# TDAR_VER_88.net
KiCad netlist of a schematic drawn in EAGLE
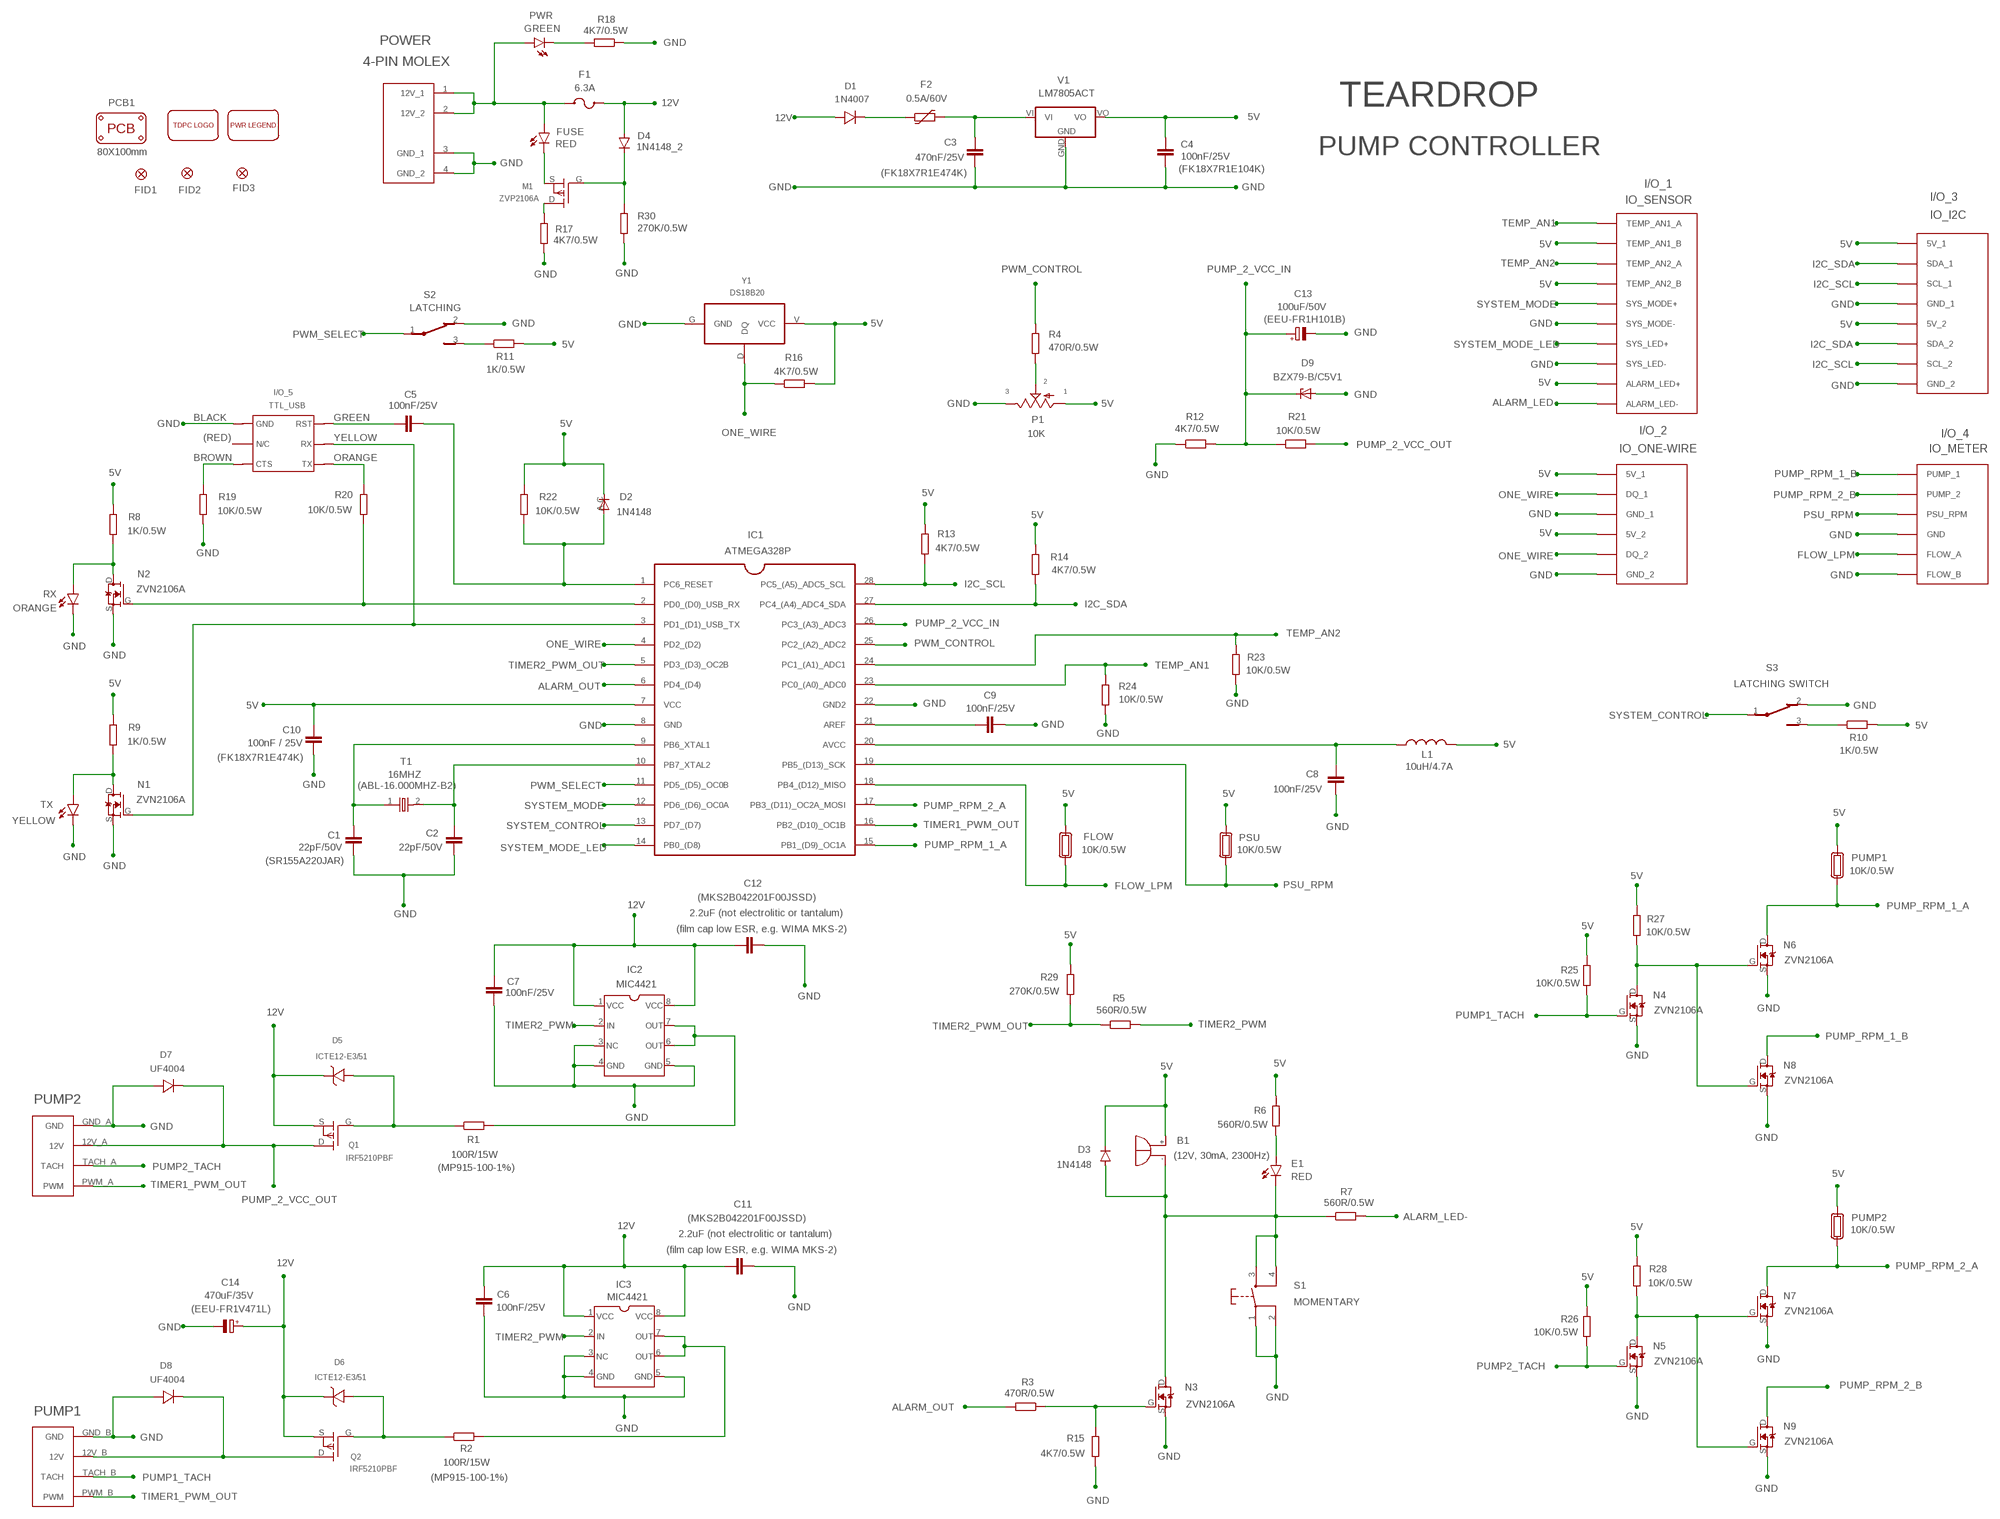
[diagram p0: schematic, sheet 1]

(export (version "E")
  (design (tool "Eeschema 10.0.6"))
  (components
    (comp (ref "B1")
      (value "(12V, 30mA, 2300Hz)")
      (footprint "eagle-import:F_TMB")
      (libsource (lib "eagle-import") (part "F/TMB"))
    )
    (comp (ref "C1")
      (value "22pF/50V")
      (footprint "eagle-import:MLCC_CERAMIC_12")
      (libsource (lib "eagle-import") (part "MLCC_CERAMIC_12"))
    )
    (comp (ref "C2")
      (value "22pF/50V")
      (footprint "eagle-import:MLCC_CERAMIC_11")
      (libsource (lib "eagle-import") (part "MLCC_CERAMIC_11"))
    )
    (comp (ref "C3")
      (value "470nF/25V")
      (footprint "eagle-import:MLCC_CERAMIC_8")
      (libsource (lib "eagle-import") (part "MLCC_CERAMIC_8"))
    )
    (comp (ref "C4")
      (value "100nF/25V")
      (footprint "eagle-import:MLCC_CERAMIC")
      (libsource (lib "eagle-import") (part "MLCC_CERAMIC"))
    )
    (comp (ref "C5")
      (value "100nF/25V")
      (footprint "eagle-import:MLCC_CERAMIC")
      (libsource (lib "eagle-import") (part "MLCC_CERAMIC"))
    )
    (comp (ref "C6")
      (value "100nF/25V")
      (footprint "eagle-import:MLCC_CERAMIC")
      (libsource (lib "eagle-import") (part "MLCC_CERAMIC"))
    )
    (comp (ref "C7")
      (value "100nF/25V")
      (footprint "eagle-import:MLCC_CERAMIC")
      (libsource (lib "eagle-import") (part "MLCC_CERAMIC"))
    )
    (comp (ref "C8")
      (value "100nF/25V")
      (footprint "eagle-import:MLCC_CERAMIC_7")
      (libsource (lib "eagle-import") (part "MLCC_CERAMIC_7"))
    )
    (comp (ref "C9")
      (value "100nF/25V")
      (footprint "eagle-import:MLCC_CERAMIC_7")
      (libsource (lib "eagle-import") (part "MLCC_CERAMIC_7"))
    )
    (comp (ref "C10")
      (value "100nF / 25V")
      (footprint "eagle-import:MLCC_CERAMIC_6")
      (libsource (lib "eagle-import") (part "MLCC_CERAMIC_6"))
    )
    (comp (ref "C11")
      (value "(MKS2B042201F00JSSD)")
      (footprint "eagle-import:WIMA_CAPACITOR")
      (libsource (lib "eagle-import") (part "WIMA_CAPACITOR"))
    )
    (comp (ref "C12")
      (value "(MKS2B042201F00JSSD)")
      (footprint "eagle-import:WIMA_CAPACITOR")
      (libsource (lib "eagle-import") (part "WIMA_CAPACITOR"))
    )
    (comp (ref "C13")
      (value "100uF/50V")
      (footprint "eagle-import:E5-10,5")
      (libsource (lib "eagle-import") (part "CPOL-EUE5-10.5"))
    )
    (comp (ref "C14")
      (value "470uF/35V")
      (footprint "eagle-import:E5-10,5")
      (libsource (lib "eagle-import") (part "CPOL-EUE5-10.5"))
    )
    (comp (ref "D1")
      (value "1N4007")
      (footprint "eagle-import:UF4004")
      (libsource (lib "eagle-import") (part "UF4004"))
    )
    (comp (ref "D2")
      (value "1N4148")
      (footprint "eagle-import:DO35-7")
      (libsource (lib "eagle-import") (part "1N4148DO35-7"))
    )
    (comp (ref "D3")
      (value "1N4148")
      (footprint "eagle-import:1N4148")
      (libsource (lib "eagle-import") (part "1N4148"))
    )
    (comp (ref "D4")
      (value "1N4148_2")
      (footprint "eagle-import:1N4148_2")
      (libsource (lib "eagle-import") (part "1N4148_2"))
    )
    (comp (ref "D5")
      (value "ICTE12-E3/51")
      (footprint "eagle-import:TVS_DIODE")
      (libsource (lib "eagle-import") (part "TVS_DIODE"))
    )
    (comp (ref "D6")
      (value "ICTE12-E3/51")
      (footprint "eagle-import:TVS_DIODE")
      (libsource (lib "eagle-import") (part "TVS_DIODE"))
    )
    (comp (ref "D7")
      (value "UF4004")
      (footprint "eagle-import:UF4004_2")
      (libsource (lib "eagle-import") (part "UF4004_2"))
    )
    (comp (ref "D8")
      (value "UF4004")
      (footprint "eagle-import:UF4004_2")
      (libsource (lib "eagle-import") (part "UF4004_2"))
    )
    (comp (ref "D9")
      (value "BZX79-B/C5V1")
      (footprint "eagle-import:DO34Z7")
      (libsource (lib "eagle-import") (part "BZX90"))
    )
    (comp (ref "E1")
      (value "RED")
      (footprint "eagle-import:LED_5_HORIZONTAL")
      (libsource (lib "eagle-import") (part "LED_5_HORIZONTAL"))
    )
    (comp (ref "F1")
      (value "6.3A")
      (footprint "eagle-import:FUSE_GLASS")
      (libsource (lib "eagle-import") (part "FUSE_GLASS"))
    )
    (comp (ref "F2")
      (value "0.5A/60V")
      (footprint "eagle-import:PTC")
      (libsource (lib "eagle-import") (part "PTC"))
    )
    (comp (ref "FID1")
      (value "FIDUCIAL1X2")
      (footprint "eagle-import:FIDUCIAL-1X2")
      (libsource (lib "eagle-import") (part "FIDUCIAL1X2"))
    )
    (comp (ref "FID2")
      (value "FIDUCIAL1X2")
      (footprint "eagle-import:FIDUCIAL-1X2")
      (libsource (lib "eagle-import") (part "FIDUCIAL1X2"))
    )
    (comp (ref "FID3")
      (value "FIDUCIAL1X2")
      (footprint "eagle-import:FIDUCIAL-1X2")
      (libsource (lib "eagle-import") (part "FIDUCIAL1X2"))
    )
    (comp (ref "FLOW")
      (value "10K/0.5W")
      (footprint "eagle-import:RESISTOR_SOCKET_TOP")
      (libsource (lib "eagle-import") (part "RESISTOR_SOCKET_TOP"))
    )
    (comp (ref "FUSE")
      (value "RED")
      (footprint "eagle-import:LED_1.8_LEFT")
      (libsource (lib "eagle-import") (part "LED_1.8_LEFT"))
    )
    (comp (ref "I/O_1")
      (value "IO_SENSOR")
      (footprint "eagle-import:IO_GENERAL_4")
      (libsource (lib "eagle-import") (part "IO_GENERAL_4"))
    )
    (comp (ref "I/O_2")
      (value "IO_ONE-WIRE")
      (footprint "eagle-import:I0_ONE-WIRE")
      (libsource (lib "eagle-import") (part "IO_ONE-WIRE"))
    )
    (comp (ref "I/O_3")
      (value "IO_I2C")
      (footprint "eagle-import:IO_I2C")
      (libsource (lib "eagle-import") (part "IO_I2C"))
    )
    (comp (ref "I/O_4")
      (value "IO_METER")
      (footprint "eagle-import:IO_SENSOR_4")
      (libsource (lib "eagle-import") (part "IO_SENSOR_4"))
    )
    (comp (ref "I/O_5")
      (value "TTL_USB")
      (footprint "eagle-import:TTL_USB_7")
      (libsource (lib "eagle-import") (part "TTL_USB_7"))
    )
    (comp (ref "IC1")
      (value "ATMEGA328P")
      (footprint "eagle-import:ATMEGA328P")
      (libsource (lib "eagle-import") (part "ATMEGA328P"))
    )
    (comp (ref "IC2")
      (value "MIC4421")
      (footprint "eagle-import:TC4420")
      (libsource (lib "eagle-import") (part "TC4420"))
    )
    (comp (ref "IC3")
      (value "MIC4421")
      (footprint "eagle-import:TC4420")
      (libsource (lib "eagle-import") (part "TC4420"))
    )
    (comp (ref "L1")
      (value "10uH/4.7A")
      (footprint "eagle-import:IRF24")
      (libsource (lib "eagle-import") (part "L-USIRF-24"))
    )
    (comp (ref "M1")
      (value "ZVP2106A")
      (footprint "eagle-import:ZVP2106A")
      (libsource (lib "eagle-import") (part "ZVP2106A"))
    )
    (comp (ref "N1")
      (value "ZVN2106A")
      (footprint "eagle-import:ZVN2106A")
      (libsource (lib "eagle-import") (part "ZVN2106A"))
    )
    (comp (ref "N2")
      (value "ZVN2106A")
      (footprint "eagle-import:ZVN2106A")
      (libsource (lib "eagle-import") (part "ZVN2106A"))
    )
    (comp (ref "N3")
      (value "ZVN2106A")
      (footprint "eagle-import:ZVN2106A")
      (libsource (lib "eagle-import") (part "ZVN2106A"))
    )
    (comp (ref "N4")
      (value "ZVN2106A")
      (footprint "eagle-import:ZVN2106A")
      (libsource (lib "eagle-import") (part "ZVN2106A"))
    )
    (comp (ref "N5")
      (value "ZVN2106A")
      (footprint "eagle-import:ZVN2106A")
      (libsource (lib "eagle-import") (part "ZVN2106A"))
    )
    (comp (ref "N6")
      (value "ZVN2106A")
      (footprint "eagle-import:ZVN2106A")
      (libsource (lib "eagle-import") (part "ZVN2106A"))
    )
    (comp (ref "N7")
      (value "ZVN2106A")
      (footprint "eagle-import:ZVN2106A")
      (libsource (lib "eagle-import") (part "ZVN2106A"))
    )
    (comp (ref "N8")
      (value "ZVN2106A")
      (footprint "eagle-import:ZVN2106A")
      (libsource (lib "eagle-import") (part "ZVN2106A"))
    )
    (comp (ref "N9")
      (value "ZVN2106A")
      (footprint "eagle-import:ZVN2106A")
      (libsource (lib "eagle-import") (part "ZVN2106A"))
    )
    (comp (ref "P1")
      (value "10K")
      (footprint "eagle-import:POTENTIMETER_SQUARE")
      (libsource (lib "eagle-import") (part "POTENTIMETER_SQUARE"))
    )
    (comp (ref "PCB1")
      (value "80X100mm")
      (footprint "eagle-import:DP10080_V1")
      (libsource (lib "eagle-import") (part "PCB_DP_RECTANGLE-80X100"))
    )
    (comp (ref "POWER")
      (value "4-PIN MOLEX")
      (footprint "eagle-import:MOLEX_4PIN_2")
      (libsource (lib "eagle-import") (part "MOLEX_4PIN_2"))
    )
    (comp (ref "PSU")
      (value "10K/0.5W")
      (footprint "eagle-import:RESISTOR_SOCKET_TOP")
      (libsource (lib "eagle-import") (part "RESISTOR_SOCKET_TOP"))
    )
    (comp (ref "PUMP1")
      (value "10K/0.5W")
      (footprint "eagle-import:RESISTOR_SOCKET_TOP")
      (libsource (lib "eagle-import") (part "RESISTOR_SOCKET_TOP"))
    )
    (comp (ref "PUMP2")
      (value "10K/0.5W")
      (footprint "eagle-import:RESISTOR_SOCKET_TOP")
      (libsource (lib "eagle-import") (part "RESISTOR_SOCKET_TOP"))
    )
    (comp (ref "PUMP_2")
      (value "PUMP2")
      (footprint "eagle-import:MOLEX_POWER_8_PIN_HORIZONTAL_2")
      (libsource (lib "eagle-import") (part "MOLEX_POWER_8_PIN_HORIZONTAL_2"))
    )
    (comp (ref "PWR")
      (value "GREEN")
      (footprint "eagle-import:LED_1.8_LEFT")
      (libsource (lib "eagle-import") (part "LED_1.8_LEFT"))
    )
    (comp (ref "Q1")
      (value "IRF5210PBF")
      (footprint "eagle-import:IRF5210")
      (libsource (lib "eagle-import") (part "IRF5210"))
    )
    (comp (ref "Q2")
      (value "IRF5210PBF")
      (footprint "eagle-import:IRF5210")
      (libsource (lib "eagle-import") (part "IRF5210"))
    )
    (comp (ref "R1")
      (value "100R/15W")
      (footprint "eagle-import:V234_12")
      (libsource (lib "eagle-import") (part "R-EU_V234/12"))
    )
    (comp (ref "R2")
      (value "100R/15W")
      (footprint "eagle-import:V234_12")
      (libsource (lib "eagle-import") (part "R-EU_V234/12"))
    )
    (comp (ref "R3")
      (value "470R/0.5W")
      (footprint "eagle-import:0204_5")
      (libsource (lib "eagle-import") (part "RESISTOR (REGULAR, 0.25W)_R-EU_0204/5"))
    )
    (comp (ref "R4")
      (value "470R/0.5W")
      (footprint "eagle-import:0204_5")
      (libsource (lib "eagle-import") (part "RESISTOR (REGULAR, 0.25W)_R-EU_0204/5"))
    )
    (comp (ref "R5")
      (value "560R/0.5W")
      (footprint "eagle-import:0204_5")
      (libsource (lib "eagle-import") (part "RESISTOR (REGULAR, 0.25W)_R-EU_0204/5"))
    )
    (comp (ref "R6")
      (value "560R/0.5W")
      (footprint "eagle-import:0204_5")
      (libsource (lib "eagle-import") (part "RESISTOR (REGULAR, 0.25W)_R-EU_0204/5"))
    )
    (comp (ref "R7")
      (value "560R/0.5W")
      (footprint "eagle-import:0204_5")
      (libsource (lib "eagle-import") (part "RESISTOR (REGULAR, 0.25W)_R-EU_0204/5"))
    )
    (comp (ref "R8")
      (value "1K/0.5W")
      (footprint "eagle-import:0204_5")
      (libsource (lib "eagle-import") (part "RESISTOR (REGULAR, 0.25W)_R-EU_0204/5"))
    )
    (comp (ref "R9")
      (value "1K/0.5W")
      (footprint "eagle-import:0204_5")
      (libsource (lib "eagle-import") (part "RESISTOR (REGULAR, 0.25W)_R-EU_0204/5"))
    )
    (comp (ref "R10")
      (value "1K/0.5W")
      (footprint "eagle-import:0204_5")
      (libsource (lib "eagle-import") (part "RESISTOR (REGULAR, 0.25W)_R-EU_0204/5"))
    )
    (comp (ref "R11")
      (value "1K/0.5W")
      (footprint "eagle-import:0204_5")
      (libsource (lib "eagle-import") (part "RESISTOR (REGULAR, 0.25W)_R-EU_0204/5"))
    )
    (comp (ref "R12")
      (value "4K7/0.5W")
      (footprint "eagle-import:0204_5")
      (libsource (lib "eagle-import") (part "RESISTOR (REGULAR, 0.25W)_R-EU_0204/5"))
    )
    (comp (ref "R13")
      (value "4K7/0.5W")
      (footprint "eagle-import:0204_5")
      (libsource (lib "eagle-import") (part "RESISTOR (REGULAR, 0.25W)_R-EU_0204/5"))
    )
    (comp (ref "R14")
      (value "4K7/0.5W")
      (footprint "eagle-import:0204_5")
      (libsource (lib "eagle-import") (part "RESISTOR (REGULAR, 0.25W)_R-EU_0204/5"))
    )
    (comp (ref "R15")
      (value "4K7/0.5W")
      (footprint "eagle-import:0204_5")
      (libsource (lib "eagle-import") (part "RESISTOR (REGULAR, 0.25W)_R-EU_0204/5"))
    )
    (comp (ref "R16")
      (value "4K7/0.5W")
      (footprint "eagle-import:0204_5")
      (libsource (lib "eagle-import") (part "RESISTOR (REGULAR, 0.25W)_R-EU_0204/5"))
    )
    (comp (ref "R17")
      (value "4K7/0.5W")
      (footprint "eagle-import:0204_5")
      (libsource (lib "eagle-import") (part "RESISTOR (REGULAR, 0.25W)_R-EU_0204/5"))
    )
    (comp (ref "R18")
      (value "4K7/0.5W")
      (footprint "eagle-import:0204_5")
      (libsource (lib "eagle-import") (part "RESISTOR (REGULAR, 0.25W)_R-EU_0204/5"))
    )
    (comp (ref "R19")
      (value "10K/0.5W")
      (footprint "eagle-import:0204_5")
      (libsource (lib "eagle-import") (part "RESISTOR (REGULAR, 0.25W)_R-EU_0204/5"))
    )
    (comp (ref "R20")
      (value "10K/0.5W")
      (footprint "eagle-import:0204_5")
      (libsource (lib "eagle-import") (part "RESISTOR (REGULAR, 0.25W)_R-EU_0204/5"))
    )
    (comp (ref "R21")
      (value "10K/0.5W")
      (footprint "eagle-import:0204_5")
      (libsource (lib "eagle-import") (part "RESISTOR (REGULAR, 0.25W)_R-EU_0204/5"))
    )
    (comp (ref "R22")
      (value "10K/0.5W")
      (footprint "eagle-import:0204_5")
      (libsource (lib "eagle-import") (part "RESISTOR (REGULAR, 0.25W)_R-EU_0204/5"))
    )
    (comp (ref "R23")
      (value "10K/0.5W")
      (footprint "eagle-import:0204_5")
      (libsource (lib "eagle-import") (part "RESISTOR (REGULAR, 0.25W)_R-EU_0204/5"))
    )
    (comp (ref "R24")
      (value "10K/0.5W")
      (footprint "eagle-import:0204_5")
      (libsource (lib "eagle-import") (part "RESISTOR (REGULAR, 0.25W)_R-EU_0204/5"))
    )
    (comp (ref "R25")
      (value "10K/0.5W")
      (footprint "eagle-import:0204_5")
      (libsource (lib "eagle-import") (part "RESISTOR (REGULAR, 0.25W)_R-EU_0204/5"))
    )
    (comp (ref "R26")
      (value "10K/0.5W")
      (footprint "eagle-import:0204_5")
      (libsource (lib "eagle-import") (part "RESISTOR (REGULAR, 0.25W)_R-EU_0204/5"))
    )
    (comp (ref "R27")
      (value "10K/0.5W")
      (footprint "eagle-import:0204_5")
      (libsource (lib "eagle-import") (part "RESISTOR (REGULAR, 0.25W)_R-EU_0204/5"))
    )
    (comp (ref "R28")
      (value "10K/0.5W")
      (footprint "eagle-import:0204_5")
      (libsource (lib "eagle-import") (part "RESISTOR (REGULAR, 0.25W)_R-EU_0204/5"))
    )
    (comp (ref "R29")
      (value "270K/0.5W")
      (footprint "eagle-import:0204_5")
      (libsource (lib "eagle-import") (part "RESISTOR (REGULAR, 0.25W)_R-EU_0204/5"))
    )
    (comp (ref "R30")
      (value "270K/0.5W")
      (footprint "eagle-import:0204_5")
      (libsource (lib "eagle-import") (part "RESISTOR (REGULAR, 0.25W)_R-EU_0204/5"))
    )
    (comp (ref "RX")
      (value "ORANGE")
      (footprint "eagle-import:LED_1.8_RIGHT")
      (libsource (lib "eagle-import") (part "LED_1.8_RIGHT"))
    )
    (comp (ref "S1")
      (value "MOMENTARY")
      (footprint "eagle-import:MOM_SWITCH_6.0")
      (libsource (lib "eagle-import") (part "MOM_SWITCH_6.0"))
    )
    (comp (ref "S2")
      (value "LATCHING")
      (footprint "eagle-import:SLIDING_SWITCH_5")
      (libsource (lib "eagle-import") (part "SLIDING_SWITCH_5"))
    )
    (comp (ref "S3")
      (value "LATCHING SWITCH")
      (footprint "eagle-import:SLIDING_SWITCH_4")
      (libsource (lib "eagle-import") (part "SLIDING_SWITCH_4"))
    )
    (comp (ref "T1")
      (value "16MHZ")
      (footprint "eagle-import:CRYSTAL_16MHZ")
      (libsource (lib "eagle-import") (part "CRYSTAL_16MHZ"))
    )
    (comp (ref "TX")
      (value "YELLOW")
      (footprint "eagle-import:LED_1.8_RIGHT")
      (libsource (lib "eagle-import") (part "LED_1.8_RIGHT"))
    )
    (comp (ref "U$1")
      (value "TDPC_LOGO")
      (footprint "eagle-import:TDPC_LOGO")
      (libsource (lib "eagle-import") (part "TDPC_LOGO"))
    )
    (comp (ref "U$2")
      (value "MOLEX_4PIN_LEGEND")
      (footprint "eagle-import:MOLEX_4PIN_LEGEND")
      (libsource (lib "eagle-import") (part "MOLEX_4PIN_LEGEND"))
    )
    (comp (ref "V1")
      (value "LM7805ACT")
      (footprint "eagle-import:LM7805")
      (libsource (lib "eagle-import") (part "LM7805"))
    )
    (comp (ref "Y1")
      (value "DS18B20")
      (footprint "eagle-import:DS18B20")
      (libsource (lib "eagle-import") (part "DS18B20"))
    )
  )
  (nets
    (net (code "1") (name "/5V") (class "Default")
      (node (ref "B1") (pin "+") (pinfunction "+_+") (pintype "passive"))
      (node (ref "C10") (pin "1") (pinfunction "1_1") (pintype "passive"))
      (node (ref "C4") (pin "2") (pinfunction "2_2") (pintype "passive"))
      (node (ref "D2") (pin "C") (pinfunction "C_C") (pintype "passive"))
      (node (ref "D3") (pin "C") (pinfunction "C_C") (pintype "passive"))
      (node (ref "FLOW") (pin "1") (pinfunction "1_1") (pintype "passive"))
      (node (ref "I/O_1") (pin "5V_1") (pinfunction "TEMP_AN1_B_5V_1") (pintype "passive"))
      (node (ref "I/O_1") (pin "5V_2") (pinfunction "TEMP_AN2_B_5V_2") (pintype "passive"))
      (node (ref "I/O_1") (pin "ALARM_LED+") (pinfunction "ALARM_LED+_ALARM_LED+") (pintype "passive"))
      (node (ref "I/O_2") (pin "5V_1") (pinfunction "5V_1_5V_1") (pintype "passive"))
      (node (ref "I/O_2") (pin "5V_2") (pinfunction "5V_2_5V_2") (pintype "passive"))
      (node (ref "I/O_3") (pin "5V_1") (pinfunction "5V_1_5V_1") (pintype "passive"))
      (node (ref "I/O_3") (pin "5V_2") (pinfunction "5V_2_5V_2") (pintype "passive"))
      (node (ref "IC1") (pin "7") (pinfunction "VCC_7") (pintype "bidirectional"))
      (node (ref "L1") (pin "2") (pinfunction "2_2") (pintype "passive"))
      (node (ref "P1") (pin "1") (pinfunction "A_1") (pintype "passive"))
      (node (ref "PSU") (pin "1") (pinfunction "1_1") (pintype "passive"))
      (node (ref "PUMP1") (pin "1") (pinfunction "1_1") (pintype "passive"))
      (node (ref "PUMP2") (pin "1") (pinfunction "1_1") (pintype "passive"))
      (node (ref "R10") (pin "2") (pinfunction "2_2") (pintype "passive"))
      (node (ref "R11") (pin "2") (pinfunction "2_2") (pintype "passive"))
      (node (ref "R13") (pin "2") (pinfunction "2_2") (pintype "passive"))
      (node (ref "R14") (pin "1") (pinfunction "1_1") (pintype "passive"))
      (node (ref "R16") (pin "2") (pinfunction "2_2") (pintype "passive"))
      (node (ref "R22") (pin "1") (pinfunction "1_1") (pintype "passive"))
      (node (ref "R25") (pin "1") (pinfunction "1_1") (pintype "passive"))
      (node (ref "R26") (pin "1") (pinfunction "1_1") (pintype "passive"))
      (node (ref "R27") (pin "1") (pinfunction "1_1") (pintype "passive"))
      (node (ref "R28") (pin "2") (pinfunction "2_2") (pintype "passive"))
      (node (ref "R29") (pin "1") (pinfunction "1_1") (pintype "passive"))
      (node (ref "R6") (pin "1") (pinfunction "1_1") (pintype "passive"))
      (node (ref "R8") (pin "1") (pinfunction "1_1") (pintype "passive"))
      (node (ref "R9") (pin "1") (pinfunction "1_1") (pintype "passive"))
      (node (ref "V1") (pin "VO") (pinfunction "VO_VO") (pintype "passive"))
      (node (ref "Y1") (pin "V") (pinfunction "VCC_V") (pintype "passive"))
    )
    (net (code "2") (name "/12V") (class "Default")
      (node (ref "C11") (pin "1") (pinfunction "1_1") (pintype "passive"))
      (node (ref "C12") (pin "1") (pinfunction "1_1") (pintype "passive"))
      (node (ref "C14") (pin "+") (pinfunction "+_+") (pintype "passive"))
      (node (ref "C6") (pin "2") (pinfunction "2_2") (pintype "passive"))
      (node (ref "C7") (pin "2") (pinfunction "2_2") (pintype "passive"))
      (node (ref "D1") (pin "A") (pinfunction "A_A") (pintype "passive"))
      (node (ref "D4") (pin "A") (pinfunction "A_A") (pintype "passive"))
      (node (ref "D5") (pin "C") (pinfunction "C_C") (pintype "passive"))
      (node (ref "D6") (pin "C") (pinfunction "C_C") (pintype "passive"))
      (node (ref "F1") (pin "2") (pinfunction "2_2") (pintype "passive"))
      (node (ref "IC2") (pin "1") (pinfunction "1_1") (pintype "passive"))
      (node (ref "IC2") (pin "8") (pinfunction "8_8") (pintype "passive"))
      (node (ref "IC3") (pin "1") (pinfunction "1_1") (pintype "passive"))
      (node (ref "IC3") (pin "8") (pinfunction "8_8") (pintype "passive"))
      (node (ref "Q1") (pin "S") (pinfunction "S_S") (pintype "passive"))
      (node (ref "Q2") (pin "S") (pinfunction "S_S") (pintype "passive"))
    )
    (net (code "3") (name "/ALARM_LED-") (class "Default")
      (node (ref "I/O_1") (pin "ALARM_LED-") (pinfunction "ALARM_LED-_ALARM_LED-") (pintype "passive"))
      (node (ref "R7") (pin "2") (pinfunction "2_2") (pintype "passive"))
    )
    (net (code "4") (name "/ALARM_OUT") (class "Default")
      (node (ref "IC1") (pin "6") (pinfunction "PD4_(D4)_6") (pintype "bidirectional"))
      (node (ref "R3") (pin "2") (pinfunction "2_2") (pintype "passive"))
    )
    (net (code "5") (name "/FLOW_LPM") (class "Default")
      (node (ref "FLOW") (pin "2") (pinfunction "2_2") (pintype "passive"))
      (node (ref "I/O_4") (pin "FLOW_A") (pinfunction "FLOW_A_FLOW_A") (pintype "passive"))
      (node (ref "IC1") (pin "18") (pinfunction "PB4_(D12)_MISO_18") (pintype "bidirectional"))
    )
    (net (code "6") (name "/GND") (class "Default")
      (node (ref "C1") (pin "2") (pinfunction "2_2") (pintype "passive"))
      (node (ref "C10") (pin "2") (pinfunction "2_2") (pintype "passive"))
      (node (ref "C11") (pin "2") (pinfunction "2_2") (pintype "passive"))
      (node (ref "C12") (pin "2") (pinfunction "2_2") (pintype "passive"))
      (node (ref "C13") (pin "-") (pinfunction "-_-") (pintype "passive"))
      (node (ref "C14") (pin "-") (pinfunction "-_-") (pintype "passive"))
      (node (ref "C2") (pin "2") (pinfunction "2_2") (pintype "passive"))
      (node (ref "C3") (pin "2") (pinfunction "2_2") (pintype "passive"))
      (node (ref "C4") (pin "1") (pinfunction "1_1") (pintype "passive"))
      (node (ref "C6") (pin "1") (pinfunction "1_1") (pintype "passive"))
      (node (ref "C7") (pin "1") (pinfunction "1_1") (pintype "passive"))
      (node (ref "C8") (pin "2") (pinfunction "2_2") (pintype "passive"))
      (node (ref "C9") (pin "2") (pinfunction "2_2") (pintype "passive"))
      (node (ref "D7") (pin "A") (pinfunction "A_A") (pintype "passive"))
      (node (ref "D8") (pin "A") (pinfunction "A_A") (pintype "passive"))
      (node (ref "D9") (pin "A") (pinfunction "A_A") (pintype "passive"))
      (node (ref "I/O_1") (pin "SYSTEM_LED-") (pinfunction "SYS_LED-_SYSTEM_LED-") (pintype "passive"))
      (node (ref "I/O_1") (pin "SYSTEM_MODE-") (pinfunction "SYS_MODE-_SYSTEM_MODE-") (pintype "passive"))
      (node (ref "I/O_2") (pin "GND_1") (pinfunction "GND_1_GND_1") (pintype "passive"))
      (node (ref "I/O_2") (pin "GND_2") (pinfunction "GND_2_GND_2") (pintype "passive"))
      (node (ref "I/O_3") (pin "GND_1") (pinfunction "GND_1_GND_1") (pintype "passive"))
      (node (ref "I/O_3") (pin "GND_2") (pinfunction "GND_2_GND_2") (pintype "passive"))
      (node (ref "I/O_4") (pin "FLOW_B") (pinfunction "FLOW_B_FLOW_B") (pintype "passive"))
      (node (ref "I/O_4") (pin "GND") (pinfunction "GND_GND") (pintype "passive"))
      (node (ref "I/O_5") (pin "GND") (pinfunction "GND_GND") (pintype "passive"))
      (node (ref "IC1") (pin "22") (pinfunction "GND2_22") (pintype "bidirectional"))
      (node (ref "IC1") (pin "8") (pinfunction "GND_8") (pintype "bidirectional"))
      (node (ref "IC2") (pin "3") (pinfunction "3_3") (pintype "passive"))
      (node (ref "IC2") (pin "4") (pinfunction "4_4") (pintype "passive"))
      (node (ref "IC2") (pin "5") (pinfunction "5_5") (pintype "passive"))
      (node (ref "IC3") (pin "3") (pinfunction "3_3") (pintype "passive"))
      (node (ref "IC3") (pin "4") (pinfunction "4_4") (pintype "passive"))
      (node (ref "IC3") (pin "5") (pinfunction "5_5") (pintype "passive"))
      (node (ref "N1") (pin "S") (pinfunction "S_S") (pintype "passive"))
      (node (ref "N2") (pin "S") (pinfunction "S_S") (pintype "passive"))
      (node (ref "N3") (pin "S") (pinfunction "S_S") (pintype "passive"))
      (node (ref "N4") (pin "S") (pinfunction "S_S") (pintype "passive"))
      (node (ref "N5") (pin "S") (pinfunction "S_S") (pintype "passive"))
      (node (ref "N6") (pin "S") (pinfunction "S_S") (pintype "passive"))
      (node (ref "N7") (pin "S") (pinfunction "S_S") (pintype "passive"))
      (node (ref "N8") (pin "S") (pinfunction "S_S") (pintype "passive"))
      (node (ref "N9") (pin "S") (pinfunction "S_S") (pintype "passive"))
      (node (ref "P1") (pin "3") (pinfunction "E_3") (pintype "passive"))
      (node (ref "POWER") (pin "3") (pinfunction "GND_1_3") (pintype "passive"))
      (node (ref "POWER") (pin "4") (pinfunction "GND_2_4") (pintype "passive"))
      (node (ref "PUMP_2") (pin "GND_A") (pinfunction "GND_GND_A") (pintype "passive"))
      (node (ref "PUMP_2") (pin "GND_B") (pinfunction "GND_GND_B") (pintype "passive"))
      (node (ref "R12") (pin "1") (pinfunction "1_1") (pintype "passive"))
      (node (ref "R15") (pin "1") (pinfunction "1_1") (pintype "passive"))
      (node (ref "R17") (pin "2") (pinfunction "2_2") (pintype "passive"))
      (node (ref "R18") (pin "1") (pinfunction "1_1") (pintype "passive"))
      (node (ref "R19") (pin "2") (pinfunction "2_2") (pintype "passive"))
      (node (ref "R23") (pin "1") (pinfunction "1_1") (pintype "passive"))
      (node (ref "R24") (pin "2") (pinfunction "2_2") (pintype "passive"))
      (node (ref "R30") (pin "2") (pinfunction "2_2") (pintype "passive"))
      (node (ref "RX") (pin "K") (pinfunction "C_K") (pintype "passive"))
      (node (ref "S1") (pin "1") (pinfunction "1_1") (pintype "passive"))
      (node (ref "S1") (pin "2") (pinfunction "2_2") (pintype "passive"))
      (node (ref "S2") (pin "2") (pinfunction "2_2") (pintype "passive"))
      (node (ref "S3") (pin "2") (pinfunction "2_2") (pintype "passive"))
      (node (ref "TX") (pin "K") (pinfunction "C_K") (pintype "passive"))
      (node (ref "V1") (pin "GND") (pinfunction "GND_GND") (pintype "passive"))
      (node (ref "Y1") (pin "G") (pinfunction "GND_G") (pintype "passive"))
    )
    (net (code "7") (name "/I2C_SCL") (class "Default")
      (node (ref "I/O_3") (pin "SCL_1") (pinfunction "SCL_1_SCL_1") (pintype "passive"))
      (node (ref "I/O_3") (pin "SCL_2") (pinfunction "SCL_2_SCL_2") (pintype "passive"))
      (node (ref "IC1") (pin "28") (pinfunction "PC5_(A5)_ADC5_SCL_28") (pintype "bidirectional"))
      (node (ref "R13") (pin "1") (pinfunction "1_1") (pintype "passive"))
    )
    (net (code "8") (name "/I2C_SDA") (class "Default")
      (node (ref "I/O_3") (pin "SDA_1") (pinfunction "SDA_1_SDA_1") (pintype "passive"))
      (node (ref "I/O_3") (pin "SDA_2") (pinfunction "SDA_2_SDA_2") (pintype "passive"))
      (node (ref "IC1") (pin "27") (pinfunction "PC4_(A4)_ADC4_SDA_27") (pintype "bidirectional"))
      (node (ref "R14") (pin "2") (pinfunction "2_2") (pintype "passive"))
    )
    (net (code "9") (name "/ONE_WIRE") (class "Default")
      (node (ref "I/O_2") (pin "DQ_1") (pinfunction "DQ_1_DQ_1") (pintype "passive"))
      (node (ref "I/O_2") (pin "DQ_2") (pinfunction "DQ_2_DQ_2") (pintype "passive"))
      (node (ref "IC1") (pin "4") (pinfunction "PD2_(D2)_4") (pintype "bidirectional"))
      (node (ref "R16") (pin "1") (pinfunction "1_1") (pintype "passive"))
      (node (ref "Y1") (pin "D") (pinfunction "DQ_D") (pintype "passive"))
    )
    (net (code "10") (name "/PSU_RPM") (class "Default")
      (node (ref "I/O_4") (pin "PSU") (pinfunction "PSU_RPM_PSU") (pintype "passive"))
      (node (ref "IC1") (pin "19") (pinfunction "PB5_(D13)_SCK_19") (pintype "bidirectional"))
      (node (ref "PSU") (pin "2") (pinfunction "2_2") (pintype "passive"))
    )
    (net (code "11") (name "/PUMP1_TACH") (class "Default")
      (node (ref "N4") (pin "G") (pinfunction "G_G") (pintype "passive"))
      (node (ref "PUMP_2") (pin "TACH_B") (pinfunction "TACH_TACH_B") (pintype "passive"))
      (node (ref "R25") (pin "2") (pinfunction "2_2") (pintype "passive"))
    )
    (net (code "12") (name "/PUMP2_TACH") (class "Default")
      (node (ref "N5") (pin "G") (pinfunction "G_G") (pintype "passive"))
      (node (ref "PUMP_2") (pin "TACH_A") (pinfunction "TACH_TACH_A") (pintype "passive"))
      (node (ref "R26") (pin "2") (pinfunction "2_2") (pintype "passive"))
    )
    (net (code "13") (name "/PUMP_2_VCC_IN") (class "Default")
      (node (ref "C13") (pin "+") (pinfunction "+_+") (pintype "passive"))
      (node (ref "D9") (pin "C") (pinfunction "C_C") (pintype "passive"))
      (node (ref "IC1") (pin "26") (pinfunction "PC3_(A3)_ADC3_26") (pintype "bidirectional"))
      (node (ref "R12") (pin "2") (pinfunction "2_2") (pintype "passive"))
      (node (ref "R21") (pin "1") (pinfunction "1_1") (pintype "passive"))
    )
    (net (code "14") (name "/PUMP_2_VCC_OUT") (class "Default")
      (node (ref "D7") (pin "C") (pinfunction "C_C") (pintype "passive"))
      (node (ref "PUMP_2") (pin "12V_A") (pinfunction "12V_12V_A") (pintype "passive"))
      (node (ref "Q1") (pin "D") (pinfunction "D_D") (pintype "passive"))
      (node (ref "R21") (pin "2") (pinfunction "2_2") (pintype "passive"))
    )
    (net (code "15") (name "/PUMP_RPM_1_A") (class "Default")
      (node (ref "IC1") (pin "15") (pinfunction "PB1_(D9)_OC1A_15") (pintype "bidirectional"))
      (node (ref "N6") (pin "D") (pinfunction "D_D") (pintype "passive"))
      (node (ref "PUMP1") (pin "2") (pinfunction "2_2") (pintype "passive"))
    )
    (net (code "16") (name "/PUMP_RPM_1_B") (class "Default")
      (node (ref "I/O_4") (pin "PUMP_1") (pinfunction "PUMP_1_PUMP_1") (pintype "passive"))
      (node (ref "N8") (pin "D") (pinfunction "D_D") (pintype "passive"))
    )
    (net (code "17") (name "/PUMP_RPM_2_A") (class "Default")
      (node (ref "IC1") (pin "17") (pinfunction "PB3_(D11)_OC2A_MOSI_17") (pintype "bidirectional"))
      (node (ref "N7") (pin "D") (pinfunction "D_D") (pintype "passive"))
      (node (ref "PUMP2") (pin "2") (pinfunction "2_2") (pintype "passive"))
    )
    (net (code "18") (name "/PUMP_RPM_2_B") (class "Default")
      (node (ref "I/O_4") (pin "PUMP_2") (pinfunction "PUMP_2_PUMP_2") (pintype "passive"))
      (node (ref "N9") (pin "D") (pinfunction "D_D") (pintype "passive"))
    )
    (net (code "19") (name "/PWM_CONTROL") (class "Default")
      (node (ref "IC1") (pin "25") (pinfunction "PC2_(A2)_ADC2_25") (pintype "bidirectional"))
      (node (ref "R4") (pin "2") (pinfunction "2_2") (pintype "passive"))
    )
    (net (code "20") (name "/PWM_SELECT") (class "Default")
      (node (ref "IC1") (pin "11") (pinfunction "PD5_(D5)_OC0B_11") (pintype "bidirectional"))
      (node (ref "S2") (pin "1") (pinfunction "1_1") (pintype "passive"))
    )
    (net (code "21") (name "/SYSTEM_CONTROL") (class "Default")
      (node (ref "IC1") (pin "13") (pinfunction "PD7_(D7)_13") (pintype "bidirectional"))
      (node (ref "S3") (pin "1") (pinfunction "1_1") (pintype "passive"))
    )
    (net (code "22") (name "/SYSTEM_MODE") (class "Default")
      (node (ref "I/O_1") (pin "SYSTEM_MODE+") (pinfunction "SYS_MODE+_SYSTEM_MODE+") (pintype "passive"))
      (node (ref "IC1") (pin "12") (pinfunction "PD6_(D6)_OC0A_12") (pintype "bidirectional"))
    )
    (net (code "23") (name "/SYSTEM_MODE_LED") (class "Default")
      (node (ref "I/O_1") (pin "SYSTEM_LED+") (pinfunction "SYS_LED+_SYSTEM_LED+") (pintype "passive"))
      (node (ref "IC1") (pin "14") (pinfunction "PB0_(D8)_14") (pintype "bidirectional"))
    )
    (net (code "24") (name "/TEMP_AN1") (class "Default")
      (node (ref "I/O_1") (pin "TEMP_AN1") (pinfunction "TEMP_AN1_A_TEMP_AN1") (pintype "passive"))
      (node (ref "IC1") (pin "23") (pinfunction "PC0_(A0)_ADC0_23") (pintype "bidirectional"))
      (node (ref "R24") (pin "1") (pinfunction "1_1") (pintype "passive"))
    )
    (net (code "25") (name "/TEMP_AN2") (class "Default")
      (node (ref "I/O_1") (pin "TEMP_AN2") (pinfunction "TEMP_AN2_A_TEMP_AN2") (pintype "passive"))
      (node (ref "IC1") (pin "24") (pinfunction "PC1_(A1)_ADC1_24") (pintype "bidirectional"))
      (node (ref "R23") (pin "2") (pinfunction "2_2") (pintype "passive"))
    )
    (net (code "26") (name "/TIMER1_PWM_OUT") (class "Default")
      (node (ref "IC1") (pin "16") (pinfunction "PB2_(D10)_OC1B_16") (pintype "bidirectional"))
      (node (ref "PUMP_2") (pin "PWM_A") (pinfunction "PWM_PWM_A") (pintype "passive"))
      (node (ref "PUMP_2") (pin "PWM_B") (pinfunction "PWM_PWM_B") (pintype "passive"))
    )
    (net (code "27") (name "/TIMER2_PWM") (class "Default")
      (node (ref "IC2") (pin "2") (pinfunction "2_2") (pintype "passive"))
      (node (ref "IC3") (pin "2") (pinfunction "2_2") (pintype "passive"))
      (node (ref "R5") (pin "2") (pinfunction "2_2") (pintype "passive"))
    )
    (net (code "28") (name "/TIMER2_PWM_OUT") (class "Default")
      (node (ref "IC1") (pin "5") (pinfunction "PD3_(D3)_OC2B_5") (pintype "bidirectional"))
      (node (ref "R29") (pin "2") (pinfunction "2_2") (pintype "passive"))
      (node (ref "R5") (pin "1") (pinfunction "1_1") (pintype "passive"))
    )
    (net (code "29") (name "Net-(C3-Pad1)") (class "Default")
      (node (ref "C3") (pin "1") (pinfunction "1_1") (pintype "passive"))
      (node (ref "F2") (pin "2") (pinfunction "2_2") (pintype "passive"))
      (node (ref "V1") (pin "VI") (pinfunction "VI_VI") (pintype "input"))
    )
    (net (code "30") (name "Net-(C5-Pad2)") (class "Default")
      (node (ref "C5") (pin "2") (pinfunction "2_2") (pintype "passive"))
      (node (ref "I/O_5") (pin "RST") (pinfunction "RST_RST") (pintype "passive"))
    )
    (net (code "31") (name "Net-(D1-PadC)") (class "Default")
      (node (ref "D1") (pin "C") (pinfunction "C_C") (pintype "passive"))
      (node (ref "F2") (pin "1") (pinfunction "1_1") (pintype "passive"))
    )
    (net (code "32") (name "Net-(D4-PadC)") (class "Default")
      (node (ref "D4") (pin "C") (pinfunction "C_C") (pintype "passive"))
      (node (ref "M1") (pin "G") (pinfunction "G_G") (pintype "passive"))
      (node (ref "R30") (pin "1") (pinfunction "1_1") (pintype "passive"))
    )
    (net (code "33") (name "Net-(D5-PadA)") (class "Default")
      (node (ref "D5") (pin "A") (pinfunction "A_A") (pintype "passive"))
      (node (ref "Q1") (pin "G") (pinfunction "G_G") (pintype "passive"))
      (node (ref "R1") (pin "1") (pinfunction "1_1") (pintype "passive"))
    )
    (net (code "34") (name "Net-(D6-PadA)") (class "Default")
      (node (ref "D6") (pin "A") (pinfunction "A_A") (pintype "passive"))
      (node (ref "Q2") (pin "G") (pinfunction "G_G") (pintype "passive"))
      (node (ref "R2") (pin "1") (pinfunction "1_1") (pintype "passive"))
    )
    (net (code "35") (name "Net-(E1-C)") (class "Default")
      (node (ref "B1") (pin "-") (pinfunction "-_-") (pintype "passive"))
      (node (ref "D3") (pin "A") (pinfunction "A_A") (pintype "passive"))
      (node (ref "E1") (pin "K") (pinfunction "C_K") (pintype "passive"))
      (node (ref "N3") (pin "D") (pinfunction "D_D") (pintype "passive"))
      (node (ref "R7") (pin "1") (pinfunction "1_1") (pintype "passive"))
      (node (ref "S1") (pin "3") (pinfunction "3_3") (pintype "passive"))
      (node (ref "S1") (pin "4") (pinfunction "4_4") (pintype "passive"))
    )
    (net (code "36") (name "Net-(E1-PadA)") (class "Default")
      (node (ref "E1") (pin "A") (pinfunction "A_A") (pintype "passive"))
      (node (ref "R6") (pin "2") (pinfunction "2_2") (pintype "passive"))
    )
    (net (code "37") (name "Net-(FUSE-C)") (class "Default")
      (node (ref "FUSE") (pin "K") (pinfunction "C_K") (pintype "passive"))
      (node (ref "M1") (pin "S") (pinfunction "S_S") (pintype "passive"))
    )
    (net (code "38") (name "Net-(I/O_5-PadCTS)") (class "Default")
      (node (ref "I/O_5") (pin "CTS") (pinfunction "CTS_CTS") (pintype "passive"))
      (node (ref "R19") (pin "1") (pinfunction "1_1") (pintype "passive"))
    )
    (net (code "39") (name "Net-(I/O_5-PadTX)") (class "Default")
      (node (ref "I/O_5") (pin "TX") (pinfunction "TX_TX") (pintype "passive"))
      (node (ref "R20") (pin "1") (pinfunction "1_1") (pintype "passive"))
    )
    (net (code "40") (name "Net-(IC1-AREF)") (class "Default")
      (node (ref "C9") (pin "1") (pinfunction "1_1") (pintype "passive"))
      (node (ref "IC1") (pin "21") (pinfunction "AREF_21") (pintype "bidirectional"))
    )
    (net (code "41") (name "Net-(IC1-AVCC)") (class "Default")
      (node (ref "C8") (pin "1") (pinfunction "1_1") (pintype "passive"))
      (node (ref "IC1") (pin "20") (pinfunction "AVCC_20") (pintype "bidirectional"))
      (node (ref "L1") (pin "1") (pinfunction "1_1") (pintype "passive"))
    )
    (net (code "42") (name "Net-(IC1-PB6_XTAL1)") (class "Default")
      (node (ref "C1") (pin "1") (pinfunction "1_1") (pintype "passive"))
      (node (ref "IC1") (pin "9") (pinfunction "PB6_XTAL1_9") (pintype "bidirectional"))
      (node (ref "T1") (pin "1") (pinfunction "1_1") (pintype "passive"))
    )
    (net (code "43") (name "Net-(IC1-PB7_XTAL2)") (class "Default")
      (node (ref "C2") (pin "1") (pinfunction "1_1") (pintype "passive"))
      (node (ref "IC1") (pin "10") (pinfunction "PB7_XTAL2_10") (pintype "bidirectional"))
      (node (ref "T1") (pin "2") (pinfunction "2_2") (pintype "passive"))
    )
    (net (code "44") (name "Net-(IC1-PC6_RESET)") (class "Default")
      (node (ref "C5") (pin "1") (pinfunction "1_1") (pintype "passive"))
      (node (ref "D2") (pin "A") (pinfunction "A_A") (pintype "passive"))
      (node (ref "IC1") (pin "1") (pinfunction "PC6_RESET_1") (pintype "bidirectional"))
      (node (ref "R22") (pin "2") (pinfunction "2_2") (pintype "passive"))
    )
    (net (code "45") (name "Net-(IC1-PD0_(D0)_USB_RX)") (class "Default")
      (node (ref "IC1") (pin "2") (pinfunction "PD0_(D0)_USB_RX_2") (pintype "bidirectional"))
      (node (ref "N2") (pin "G") (pinfunction "G_G") (pintype "passive"))
      (node (ref "R20") (pin "2") (pinfunction "2_2") (pintype "passive"))
    )
    (net (code "46") (name "Net-(IC1-PD1_(D1)_USB_TX)") (class "Default")
      (node (ref "I/O_5") (pin "RX") (pinfunction "RX_RX") (pintype "passive"))
      (node (ref "IC1") (pin "3") (pinfunction "PD1_(D1)_USB_TX_3") (pintype "bidirectional"))
      (node (ref "N1") (pin "G") (pinfunction "G_G") (pintype "passive"))
    )
    (net (code "47") (name "Net-(IC2-Pad6)") (class "Default")
      (node (ref "IC2") (pin "6") (pinfunction "6_6") (pintype "passive"))
      (node (ref "IC2") (pin "7") (pinfunction "7_7") (pintype "passive"))
      (node (ref "R1") (pin "2") (pinfunction "2_2") (pintype "passive"))
    )
    (net (code "48") (name "Net-(IC3-Pad6)") (class "Default")
      (node (ref "IC3") (pin "6") (pinfunction "6_6") (pintype "passive"))
      (node (ref "IC3") (pin "7") (pinfunction "7_7") (pintype "passive"))
      (node (ref "R2") (pin "2") (pinfunction "2_2") (pintype "passive"))
    )
    (net (code "49") (name "Net-(M1-PadD)") (class "Default")
      (node (ref "M1") (pin "D") (pinfunction "D_D") (pintype "passive"))
      (node (ref "R17") (pin "1") (pinfunction "1_1") (pintype "passive"))
    )
    (net (code "50") (name "Net-(N1-PadD)") (class "Default")
      (node (ref "N1") (pin "D") (pinfunction "D_D") (pintype "passive"))
      (node (ref "R9") (pin "2") (pinfunction "2_2") (pintype "passive"))
      (node (ref "TX") (pin "A") (pinfunction "A_A") (pintype "passive"))
    )
    (net (code "51") (name "Net-(N2-PadD)") (class "Default")
      (node (ref "N2") (pin "D") (pinfunction "D_D") (pintype "passive"))
      (node (ref "R8") (pin "2") (pinfunction "2_2") (pintype "passive"))
      (node (ref "RX") (pin "A") (pinfunction "A_A") (pintype "passive"))
    )
    (net (code "52") (name "Net-(N3-PadG)") (class "Default")
      (node (ref "N3") (pin "G") (pinfunction "G_G") (pintype "passive"))
      (node (ref "R15") (pin "2") (pinfunction "2_2") (pintype "passive"))
      (node (ref "R3") (pin "1") (pinfunction "1_1") (pintype "passive"))
    )
    (net (code "53") (name "Net-(N4-PadD)") (class "Default")
      (node (ref "N4") (pin "D") (pinfunction "D_D") (pintype "passive"))
      (node (ref "N6") (pin "G") (pinfunction "G_G") (pintype "passive"))
      (node (ref "N8") (pin "G") (pinfunction "G_G") (pintype "passive"))
      (node (ref "R27") (pin "2") (pinfunction "2_2") (pintype "passive"))
    )
    (net (code "54") (name "Net-(N5-PadD)") (class "Default")
      (node (ref "N5") (pin "D") (pinfunction "D_D") (pintype "passive"))
      (node (ref "N7") (pin "G") (pinfunction "G_G") (pintype "passive"))
      (node (ref "N9") (pin "G") (pinfunction "G_G") (pintype "passive"))
      (node (ref "R28") (pin "1") (pinfunction "1_1") (pintype "passive"))
    )
    (net (code "55") (name "Net-(P1-S)") (class "Default")
      (node (ref "P1") (pin "2") (pinfunction "S_2") (pintype "passive"))
      (node (ref "R4") (pin "1") (pinfunction "1_1") (pintype "passive"))
    )
    (net (code "56") (name "Net-(POWER-12V_1)") (class "Default")
      (node (ref "F1") (pin "1") (pinfunction "1_1") (pintype "passive"))
      (node (ref "FUSE") (pin "A") (pinfunction "A_A") (pintype "passive"))
      (node (ref "POWER") (pin "1") (pinfunction "12V_1_1") (pintype "passive"))
      (node (ref "POWER") (pin "2") (pinfunction "12V_2_2") (pintype "passive"))
      (node (ref "PWR") (pin "A") (pinfunction "A_A") (pintype "passive"))
    )
    (net (code "57") (name "Net-(PUMP_2B-12V)") (class "Default")
      (node (ref "D8") (pin "C") (pinfunction "C_C") (pintype "passive"))
      (node (ref "PUMP_2") (pin "12V_B") (pinfunction "12V_12V_B") (pintype "passive"))
      (node (ref "Q2") (pin "D") (pinfunction "D_D") (pintype "passive"))
    )
    (net (code "58") (name "Net-(PWR-C)") (class "Default")
      (node (ref "PWR") (pin "K") (pinfunction "C_K") (pintype "passive"))
      (node (ref "R18") (pin "2") (pinfunction "2_2") (pintype "passive"))
    )
    (net (code "59") (name "Net-(R10-Pad1)") (class "Default")
      (node (ref "R10") (pin "1") (pinfunction "1_1") (pintype "passive"))
      (node (ref "S3") (pin "3") (pinfunction "3_3") (pintype "passive"))
    )
    (net (code "60") (name "Net-(R11-Pad1)") (class "Default")
      (node (ref "R11") (pin "1") (pinfunction "1_1") (pintype "passive"))
      (node (ref "S2") (pin "3") (pinfunction "3_3") (pintype "passive"))
    )
  )
)
